# Cub.net
KiCad netlist of a schematic drawn in EAGLE
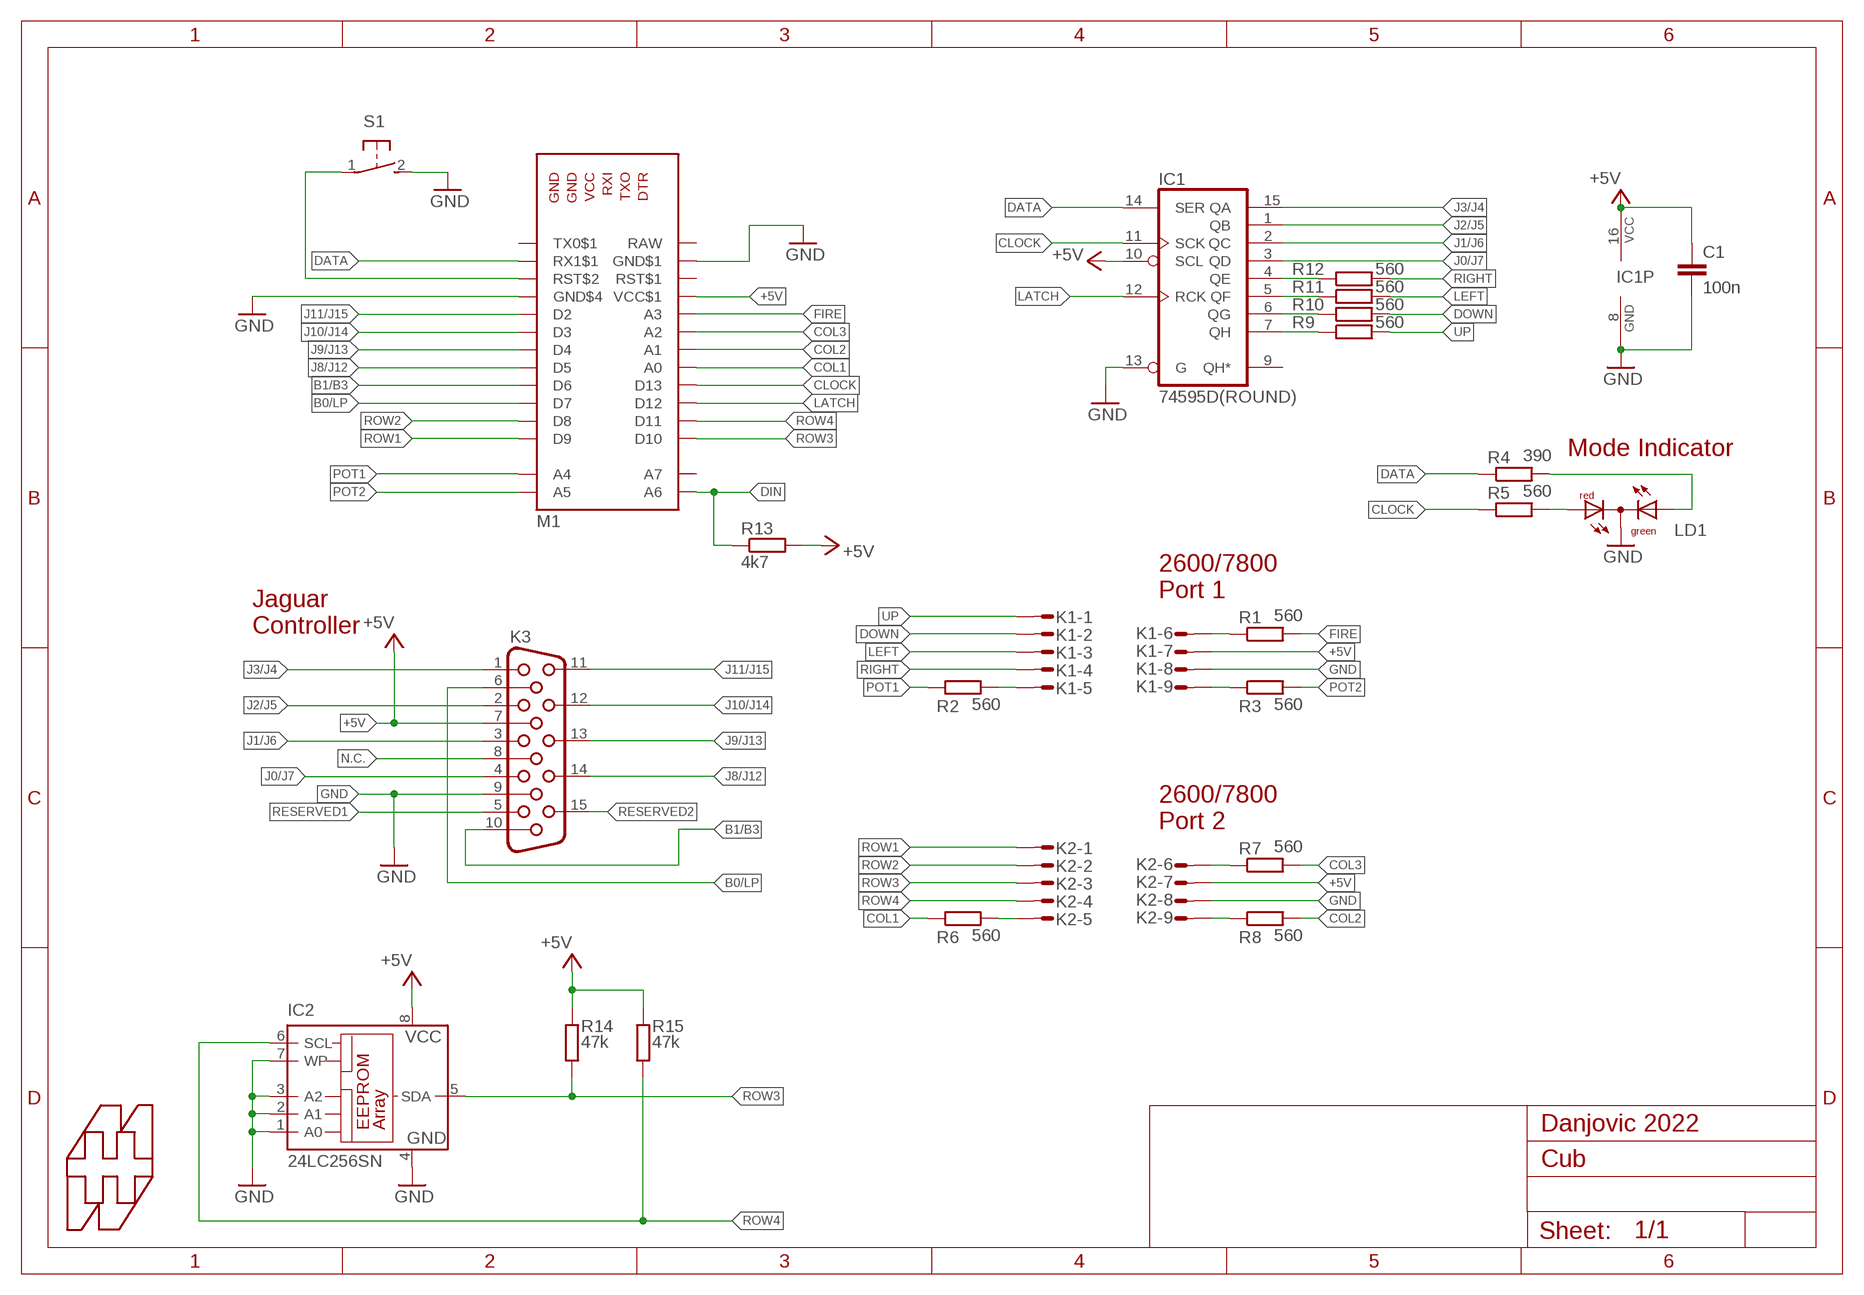
[diagram p0: schematic, sheet 1]

(export (version "E")
  (design (tool "Eeschema 10.0.6"))
  (components
    (comp (ref "C1")
      (value "100n")
      (footprint "eagle-import:C050-024X044")
      (libsource (lib "eagle-import") (part "C-EU050-024X044"))
    )
    (comp (ref "IC1")
      (value "74595D(ROUND)")
      (footprint "eagle-import:DIL16-ROUND")
      (libsource (lib "eagle-import") (part "74595D(ROUND)"))
    )
    (comp (ref "IC2")
      (value "24LC256SN")
      (footprint "eagle-import:SO-08")
      (fields (field (name "MF") "MICROCHIP") (field (name "MPN") "24LC256-I/SN"))
      (libsource (lib "eagle-import") (part "24SNLC256"))
    )
    (comp (ref "K1")
      (value "S09P")
      (footprint "eagle-import:S09P")
      (libsource (lib "eagle-import") (part "S09P"))
    )
    (comp (ref "K2")
      (value "S09P")
      (footprint "eagle-import:S09P")
      (libsource (lib "eagle-import") (part "S09P"))
    )
    (comp (ref "K3")
      (value "HF15H")
      (footprint "eagle-import:HDF15H")
      (libsource (lib "eagle-import") (part "HF15H"))
    )
    (comp (ref "LD1")
      (value "DUOLED-RG-C")
      (footprint "eagle-import:DUOLED-C-5MM")
      (libsource (lib "eagle-import") (part "DUOLED-RG-C"))
    )
    (comp (ref "M1")
      (value "ARDUINO_PRO_MINI_SIDE_ONLY")
      (footprint "eagle-import:ARDUNIO_PRO_MINI_SIDE_ONLY")
      (libsource (lib "eagle-import") (part "ARDUINO_PRO_MINI_SIDE_ONLY"))
    )
    (comp (ref "R1")
      (value "560")
      (footprint "eagle-import:0204_7")
      (libsource (lib "eagle-import") (part "R-EU_0204/7"))
    )
    (comp (ref "R2")
      (value "560")
      (footprint "eagle-import:0204_7")
      (libsource (lib "eagle-import") (part "R-EU_0204/7"))
    )
    (comp (ref "R3")
      (value "560")
      (footprint "eagle-import:0204_7")
      (libsource (lib "eagle-import") (part "R-EU_0204/7"))
    )
    (comp (ref "R4")
      (value "390")
      (footprint "eagle-import:0204_7")
      (libsource (lib "eagle-import") (part "R-EU_0204/7"))
    )
    (comp (ref "R5")
      (value "560")
      (footprint "eagle-import:0204_7")
      (libsource (lib "eagle-import") (part "R-EU_0204/7"))
    )
    (comp (ref "R6")
      (value "560")
      (footprint "eagle-import:0204_7")
      (libsource (lib "eagle-import") (part "R-EU_0204/7"))
    )
    (comp (ref "R7")
      (value "560")
      (footprint "eagle-import:0204_7")
      (libsource (lib "eagle-import") (part "R-EU_0204/7"))
    )
    (comp (ref "R8")
      (value "560")
      (footprint "eagle-import:0204_7")
      (libsource (lib "eagle-import") (part "R-EU_0204/7"))
    )
    (comp (ref "R9")
      (value "560")
      (footprint "eagle-import:0204_7")
      (libsource (lib "eagle-import") (part "R-EU_0204/7"))
    )
    (comp (ref "R10")
      (value "560")
      (footprint "eagle-import:0204_7")
      (libsource (lib "eagle-import") (part "R-EU_0204/7"))
    )
    (comp (ref "R11")
      (value "560")
      (footprint "eagle-import:0204_7")
      (libsource (lib "eagle-import") (part "R-EU_0204/7"))
    )
    (comp (ref "R12")
      (value "560")
      (footprint "eagle-import:0204_7")
      (libsource (lib "eagle-import") (part "R-EU_0204/7"))
    )
    (comp (ref "R13")
      (value "4k7")
      (footprint "eagle-import:0204_7")
      (libsource (lib "eagle-import") (part "R-EU_0204/7"))
    )
    (comp (ref "R14")
      (value "47k")
      (footprint "eagle-import:0204_7")
      (libsource (lib "eagle-import") (part "R-EU_0204/7"))
    )
    (comp (ref "R15")
      (value "47k")
      (footprint "eagle-import:0204_7")
      (libsource (lib "eagle-import") (part "R-EU_0204/7"))
    )
    (comp (ref "S1")
      (value "31-XX")
      (footprint "eagle-import:B3F-31XX")
      (fields (field (name "MPN") "B3F-3100"))
      (libsource (lib "eagle-import") (part "31-XX"))
    )
    (comp (ref "U$1")
      (value "HAMMOND-1593J")
      (footprint "eagle-import:1593J")
      (libsource (lib "eagle-import") (part "HAMMOND-1593J"))
    )
  )
  (nets
    (net (code "1") (name "+5V") (class "Default")
      (node (ref "C1") (pin "1") (pinfunction "1_1") (pintype "passive"))
      (node (ref "IC1") (pin "10") (pinfunction "SCL_10") (pintype "input"))
      (node (ref "IC1") (pin "16") (pinfunction "VCC_16") (pintype "power_in"))
      (node (ref "IC2") (pin "8") (pinfunction "VCC_8") (pintype "power_in"))
      (node (ref "K1") (pin "7") (pinfunction "S_7") (pintype "passive"))
      (node (ref "K2") (pin "7") (pinfunction "S_7") (pintype "passive"))
      (node (ref "K3") (pin "7") (pinfunction "7_7") (pintype "passive"))
      (node (ref "M1") (pin "VCC$1") (pinfunction "VCC$1_VCC$1") (pintype "power_in"))
      (node (ref "R13") (pin "2") (pinfunction "2_2") (pintype "passive"))
      (node (ref "R14") (pin "2") (pinfunction "2_2") (pintype "passive"))
      (node (ref "R15") (pin "2") (pinfunction "2_2") (pintype "passive"))
    )
    (net (code "2") (name "/RAW") (class "Default")
      (node (ref "M1") (pin "RAW") (pinfunction "RAW_RAW") (pintype "power_in"))
    )
    (net (code "3") (name "B0{slash}LP") (class "Default")
      (node (ref "K3") (pin "6") (pinfunction "6_6") (pintype "passive"))
      (node (ref "M1") (pin "D7") (pinfunction "D7_D7") (pintype "bidirectional"))
    )
    (net (code "4") (name "B1{slash}B3") (class "Default")
      (node (ref "K3") (pin "10") (pinfunction "10_10") (pintype "passive"))
      (node (ref "M1") (pin "D6") (pinfunction "D6_D6") (pintype "bidirectional"))
    )
    (net (code "5") (name "CLOCK") (class "Default")
      (node (ref "IC1") (pin "11") (pinfunction "SCK_11") (pintype "input"))
      (node (ref "M1") (pin "D13") (pinfunction "D13_D13") (pintype "bidirectional"))
      (node (ref "R5") (pin "1") (pinfunction "1_1") (pintype "passive"))
    )
    (net (code "6") (name "COL1") (class "Default")
      (node (ref "M1") (pin "A0") (pinfunction "A0_A0") (pintype "bidirectional"))
      (node (ref "R6") (pin "1") (pinfunction "1_1") (pintype "passive"))
    )
    (net (code "7") (name "COL2") (class "Default")
      (node (ref "M1") (pin "A1") (pinfunction "A1_A1") (pintype "bidirectional"))
      (node (ref "R8") (pin "2") (pinfunction "2_2") (pintype "passive"))
    )
    (net (code "8") (name "COL3") (class "Default")
      (node (ref "M1") (pin "A2") (pinfunction "A2_A2") (pintype "bidirectional"))
      (node (ref "R7") (pin "2") (pinfunction "2_2") (pintype "passive"))
    )
    (net (code "9") (name "DATA") (class "Default")
      (node (ref "IC1") (pin "14") (pinfunction "SER_14") (pintype "input"))
      (node (ref "M1") (pin "RX1$1") (pinfunction "RX1$1_RX1$1") (pintype "bidirectional"))
      (node (ref "R4") (pin "1") (pinfunction "1_1") (pintype "passive"))
    )
    (net (code "10") (name "DIN") (class "Default")
      (node (ref "M1") (pin "A6") (pinfunction "A6_A6") (pintype "input"))
      (node (ref "R13") (pin "1") (pinfunction "1_1") (pintype "passive"))
    )
    (net (code "11") (name "DOWN") (class "Default")
      (node (ref "K1") (pin "2") (pinfunction "S_2") (pintype "passive"))
      (node (ref "R10") (pin "2") (pinfunction "2_2") (pintype "passive"))
    )
    (net (code "12") (name "FIRE") (class "Default")
      (node (ref "M1") (pin "A3") (pinfunction "A3_A3") (pintype "bidirectional"))
      (node (ref "R1") (pin "2") (pinfunction "2_2") (pintype "passive"))
    )
    (net (code "13") (name "GND") (class "Default")
      (node (ref "C1") (pin "2") (pinfunction "2_2") (pintype "passive"))
      (node (ref "IC1") (pin "13") (pinfunction "G_13") (pintype "input"))
      (node (ref "IC1") (pin "8") (pinfunction "GND_8") (pintype "power_in"))
      (node (ref "IC2") (pin "1") (pinfunction "A0_1") (pintype "input"))
      (node (ref "IC2") (pin "2") (pinfunction "A1_2") (pintype "input"))
      (node (ref "IC2") (pin "3") (pinfunction "A2_3") (pintype "input"))
      (node (ref "IC2") (pin "4") (pinfunction "GND_4") (pintype "power_in"))
      (node (ref "IC2") (pin "7") (pinfunction "WP_7") (pintype "input"))
      (node (ref "K1") (pin "8") (pinfunction "S_8") (pintype "passive"))
      (node (ref "K2") (pin "8") (pinfunction "S_8") (pintype "passive"))
      (node (ref "K3") (pin "9") (pinfunction "9_9") (pintype "passive"))
      (node (ref "LD1") (pin "C") (pinfunction "C_C") (pintype "passive"))
      (node (ref "M1") (pin "GDN$1") (pinfunction "GND$1_GDN$1") (pintype "power_in"))
      (node (ref "M1") (pin "GND$4") (pinfunction "GND$4_GND$4") (pintype "power_in"))
      (node (ref "S1") (pin "2") (pinfunction "S_2") (pintype "passive"))
    )
    (net (code "14") (name "J0{slash}J7") (class "Default")
      (node (ref "IC1") (pin "3") (pinfunction "QD_3") (pintype "tri_state"))
      (node (ref "K3") (pin "4") (pinfunction "4_4") (pintype "passive"))
    )
    (net (code "15") (name "J1{slash}J6") (class "Default")
      (node (ref "IC1") (pin "2") (pinfunction "QC_2") (pintype "tri_state"))
      (node (ref "K3") (pin "3") (pinfunction "3_3") (pintype "passive"))
    )
    (net (code "16") (name "J2{slash}J5") (class "Default")
      (node (ref "IC1") (pin "1") (pinfunction "QB_1") (pintype "tri_state"))
      (node (ref "K3") (pin "2") (pinfunction "2_2") (pintype "passive"))
    )
    (net (code "17") (name "J3{slash}J4") (class "Default")
      (node (ref "IC1") (pin "15") (pinfunction "QA_15") (pintype "tri_state"))
      (node (ref "K3") (pin "1") (pinfunction "1_1") (pintype "passive"))
    )
    (net (code "18") (name "J8{slash}J12") (class "Default")
      (node (ref "K3") (pin "14") (pinfunction "14_14") (pintype "passive"))
      (node (ref "M1") (pin "D5") (pinfunction "D5_D5") (pintype "bidirectional"))
    )
    (net (code "19") (name "J9{slash}J13") (class "Default")
      (node (ref "K3") (pin "13") (pinfunction "13_13") (pintype "passive"))
      (node (ref "M1") (pin "D4") (pinfunction "D4_D4") (pintype "bidirectional"))
    )
    (net (code "20") (name "J10{slash}J14") (class "Default")
      (node (ref "K3") (pin "12") (pinfunction "12_12") (pintype "passive"))
      (node (ref "M1") (pin "D3") (pinfunction "D3_D3") (pintype "bidirectional"))
    )
    (net (code "21") (name "J11{slash}J15") (class "Default")
      (node (ref "K3") (pin "11") (pinfunction "11_11") (pintype "passive"))
      (node (ref "M1") (pin "D2") (pinfunction "D2_D2") (pintype "bidirectional"))
    )
    (net (code "22") (name "LATCH") (class "Default")
      (node (ref "IC1") (pin "12") (pinfunction "RCK_12") (pintype "input"))
      (node (ref "M1") (pin "D12") (pinfunction "D12_D12") (pintype "bidirectional"))
    )
    (net (code "23") (name "LEFT") (class "Default")
      (node (ref "K1") (pin "3") (pinfunction "S_3") (pintype "passive"))
      (node (ref "R11") (pin "2") (pinfunction "2_2") (pintype "passive"))
    )
    (net (code "24") (name "N.C.") (class "Default")
      (node (ref "K3") (pin "8") (pinfunction "8_8") (pintype "passive"))
    )
    (net (code "25") (name "Net-(IC1A-QE)") (class "Default")
      (node (ref "IC1") (pin "4") (pinfunction "QE_4") (pintype "tri_state"))
      (node (ref "R12") (pin "1") (pinfunction "1_1") (pintype "passive"))
    )
    (net (code "26") (name "Net-(IC1A-QF)") (class "Default")
      (node (ref "IC1") (pin "5") (pinfunction "QF_5") (pintype "tri_state"))
      (node (ref "R11") (pin "1") (pinfunction "1_1") (pintype "passive"))
    )
    (net (code "27") (name "Net-(IC1A-QG)") (class "Default")
      (node (ref "IC1") (pin "6") (pinfunction "QG_6") (pintype "tri_state"))
      (node (ref "R10") (pin "1") (pinfunction "1_1") (pintype "passive"))
    )
    (net (code "28") (name "Net-(IC1A-QH)") (class "Default")
      (node (ref "IC1") (pin "7") (pinfunction "QH_7") (pintype "tri_state"))
      (node (ref "R9") (pin "1") (pinfunction "1_1") (pintype "passive"))
    )
    (net (code "29") (name "Net-(K1E-S)") (class "Default")
      (node (ref "K1") (pin "5") (pinfunction "S_5") (pintype "passive"))
      (node (ref "R2") (pin "2") (pinfunction "2_2") (pintype "passive"))
    )
    (net (code "30") (name "Net-(K1F-S)") (class "Default")
      (node (ref "K1") (pin "6") (pinfunction "S_6") (pintype "passive"))
      (node (ref "R1") (pin "1") (pinfunction "1_1") (pintype "passive"))
    )
    (net (code "31") (name "Net-(K1I-S)") (class "Default")
      (node (ref "K1") (pin "9") (pinfunction "S_9") (pintype "passive"))
      (node (ref "R3") (pin "1") (pinfunction "1_1") (pintype "passive"))
    )
    (net (code "32") (name "Net-(K2E-S)") (class "Default")
      (node (ref "K2") (pin "5") (pinfunction "S_5") (pintype "passive"))
      (node (ref "R6") (pin "2") (pinfunction "2_2") (pintype "passive"))
    )
    (net (code "33") (name "Net-(K2F-S)") (class "Default")
      (node (ref "K2") (pin "6") (pinfunction "S_6") (pintype "passive"))
      (node (ref "R7") (pin "1") (pinfunction "1_1") (pintype "passive"))
    )
    (net (code "34") (name "Net-(K2I-S)") (class "Default")
      (node (ref "K2") (pin "9") (pinfunction "S_9") (pintype "passive"))
      (node (ref "R8") (pin "1") (pinfunction "1_1") (pintype "passive"))
    )
    (net (code "35") (name "Net-(LD1-AG)") (class "Default")
      (node (ref "LD1") (pin "AX") (pinfunction "AG_AX") (pintype "passive"))
      (node (ref "R4") (pin "2") (pinfunction "2_2") (pintype "passive"))
    )
    (net (code "36") (name "Net-(LD1-PadAR)") (class "Default")
      (node (ref "LD1") (pin "AR") (pinfunction "AR_AR") (pintype "passive"))
      (node (ref "R5") (pin "2") (pinfunction "2_2") (pintype "passive"))
    )
    (net (code "37") (name "Net-(S1-P)") (class "Default")
      (node (ref "M1") (pin "RST$2") (pinfunction "RST$2_RST$2") (pintype "input"))
      (node (ref "S1") (pin "1") (pinfunction "P_1") (pintype "passive"))
    )
    (net (code "38") (name "POT1") (class "Default")
      (node (ref "M1") (pin "A4") (pinfunction "A4_A4") (pintype "bidirectional"))
      (node (ref "R2") (pin "1") (pinfunction "1_1") (pintype "passive"))
    )
    (net (code "39") (name "POT2") (class "Default")
      (node (ref "M1") (pin "A5") (pinfunction "A5_A5") (pintype "bidirectional"))
      (node (ref "R3") (pin "2") (pinfunction "2_2") (pintype "passive"))
    )
    (net (code "40") (name "RESERVED1") (class "Default")
      (node (ref "K3") (pin "5") (pinfunction "5_5") (pintype "passive"))
    )
    (net (code "41") (name "RESERVED2") (class "Default")
      (node (ref "K3") (pin "15") (pinfunction "15_15") (pintype "passive"))
    )
    (net (code "42") (name "RIGHT") (class "Default")
      (node (ref "K1") (pin "4") (pinfunction "S_4") (pintype "passive"))
      (node (ref "R12") (pin "2") (pinfunction "2_2") (pintype "passive"))
    )
    (net (code "43") (name "ROW1") (class "Default")
      (node (ref "K2") (pin "1") (pinfunction "S_1") (pintype "passive"))
      (node (ref "M1") (pin "D9") (pinfunction "D9_D9") (pintype "bidirectional"))
    )
    (net (code "44") (name "ROW2") (class "Default")
      (node (ref "K2") (pin "2") (pinfunction "S_2") (pintype "passive"))
      (node (ref "M1") (pin "D8") (pinfunction "D8_D8") (pintype "bidirectional"))
    )
    (net (code "45") (name "ROW3") (class "Default")
      (node (ref "IC2") (pin "5") (pinfunction "SDA_5") (pintype "bidirectional"))
      (node (ref "K2") (pin "3") (pinfunction "S_3") (pintype "passive"))
      (node (ref "M1") (pin "D10") (pinfunction "D10_D10") (pintype "bidirectional"))
      (node (ref "R14") (pin "1") (pinfunction "1_1") (pintype "passive"))
    )
    (net (code "46") (name "ROW4") (class "Default")
      (node (ref "IC2") (pin "6") (pinfunction "SCL_6") (pintype "input"))
      (node (ref "K2") (pin "4") (pinfunction "S_4") (pintype "passive"))
      (node (ref "M1") (pin "D11") (pinfunction "D11_D11") (pintype "bidirectional"))
      (node (ref "R15") (pin "1") (pinfunction "1_1") (pintype "passive"))
    )
    (net (code "47") (name "UP") (class "Default")
      (node (ref "K1") (pin "1") (pinfunction "S_1") (pintype "passive"))
      (node (ref "R9") (pin "2") (pinfunction "2_2") (pintype "passive"))
    )
    (net (code "48") (name "unconnected-(IC1A-QH*-Pad9)") (class "Default")
      (node (ref "IC1") (pin "9") (pinfunction "QH*_9") (pintype "tri_state"))
    )
    (net (code "49") (name "unconnected-(M1-PadA7)") (class "Default")
      (node (ref "M1") (pin "A7") (pinfunction "A7_A7") (pintype "input"))
    )
    (net (code "50") (name "unconnected-(M1-PadRST$1)") (class "Default")
      (node (ref "M1") (pin "RST$1") (pinfunction "RST$1_RST$1") (pintype "input"))
    )
    (net (code "51") (name "unconnected-(M1-PadTX0$1)") (class "Default")
      (node (ref "M1") (pin "TX0$1") (pinfunction "TX0$1_TX0$1") (pintype "bidirectional"))
    )
  )
)
